# stm32devboard_f401ccu6.net
KiCad netlist of a schematic drawn in EasyEDA Pro
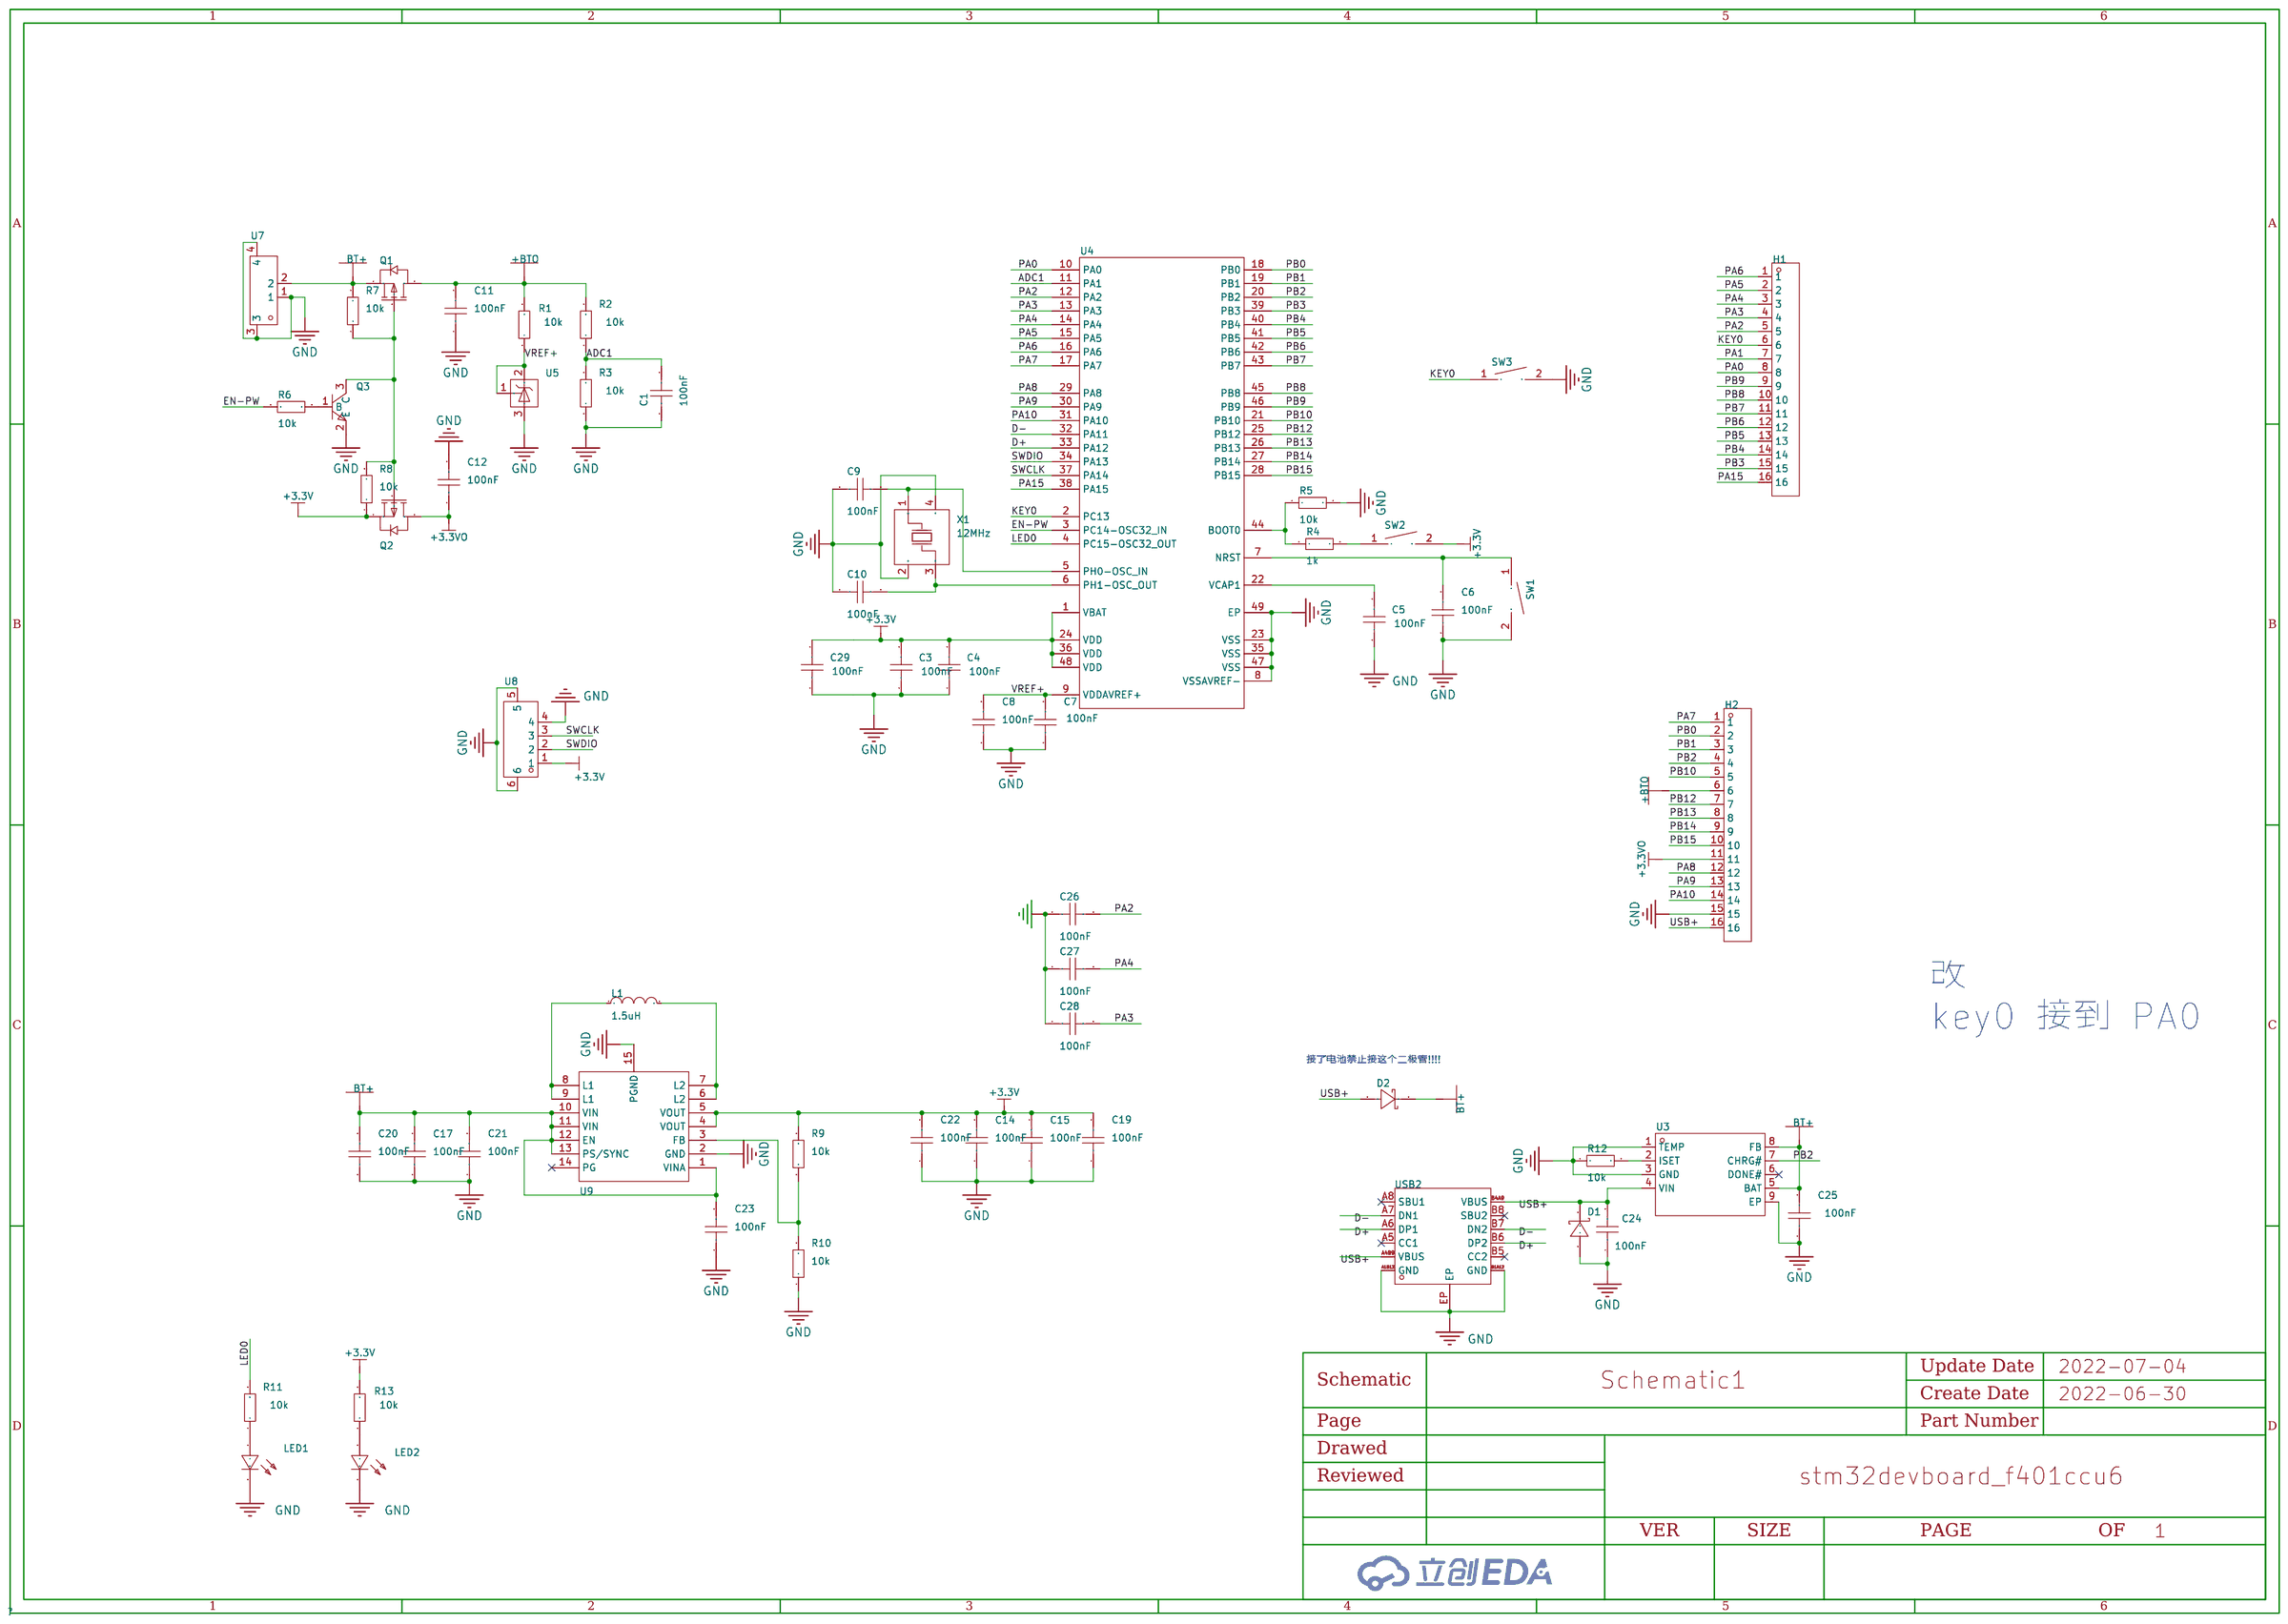
[diagram p0: schematic sheet]

(export (version "E")
  (design (tool "Eeschema 10.0.6"))
  (components
    (comp (ref "C1")
      (value "100nF")
      (footprint "easyedapro:C0402")
      (description "容值:100nF;精度:±10%;额定电压:25V;温度系数:X7R;")
      (fields (field (name "Manufacturer Part") "FN15X104K250PNG") (field (name "Manufacturer") "PSA(信昌电陶)"))
      (libsource (lib "easyedapro") (part "FN15X104K250PNG"))
    )
    (comp (ref "C3")
      (value "100nF")
      (footprint "easyedapro:C0603")
      (description "容值:100nF;精度:±10%;额定电压:50V;温度系数:X7R;")
      (fields
        (field (name "Manufacturer Part") "CC0603KRX7R9BB104")
        (field (name "Manufacturer") "YAGEO(国巨)")
      )
      (libsource (lib "easyedapro") (part "CC0603KRX7R9BB104"))
    )
    (comp (ref "C4")
      (value "100nF")
      (footprint "easyedapro:C0603")
      (description "容值:100nF;精度:±10%;额定电压:50V;温度系数:X7R;")
      (fields
        (field (name "Manufacturer Part") "CC0603KRX7R9BB104")
        (field (name "Manufacturer") "YAGEO(国巨)")
      )
      (libsource (lib "easyedapro") (part "CC0603KRX7R9BB104"))
    )
    (comp (ref "C5")
      (value "100nF")
      (footprint "easyedapro:C0603")
      (description "容值:100nF;精度:±10%;额定电压:50V;温度系数:X7R;")
      (fields
        (field (name "Manufacturer Part") "CC0603KRX7R9BB104")
        (field (name "Manufacturer") "YAGEO(国巨)")
      )
      (libsource (lib "easyedapro") (part "CC0603KRX7R9BB104"))
    )
    (comp (ref "C6")
      (value "100nF")
      (footprint "easyedapro:C0603")
      (description "容值:100nF;精度:±10%;额定电压:50V;温度系数:X7R;")
      (fields
        (field (name "Manufacturer Part") "CC0603KRX7R9BB104")
        (field (name "Manufacturer") "YAGEO(国巨)")
      )
      (libsource (lib "easyedapro") (part "CC0603KRX7R9BB104"))
    )
    (comp (ref "C7")
      (value "100nF")
      (footprint "easyedapro:C0603")
      (description "容值:100nF;精度:±10%;额定电压:50V;温度系数:X7R;")
      (fields
        (field (name "Manufacturer Part") "CC0603KRX7R9BB104")
        (field (name "Manufacturer") "YAGEO(国巨)")
      )
      (libsource (lib "easyedapro") (part "CC0603KRX7R9BB104"))
    )
    (comp (ref "C8")
      (value "100nF")
      (footprint "easyedapro:C0603")
      (description "容值:100nF;精度:±10%;额定电压:50V;温度系数:X7R;")
      (fields
        (field (name "Manufacturer Part") "CC0603KRX7R9BB104")
        (field (name "Manufacturer") "YAGEO(国巨)")
      )
      (libsource (lib "easyedapro") (part "CC0603KRX7R9BB104"))
    )
    (comp (ref "C9")
      (value "100nF")
      (footprint "easyedapro:C0603")
      (description "容值:100nF;精度:±10%;额定电压:50V;温度系数:X7R;")
      (fields
        (field (name "Manufacturer Part") "CC0603KRX7R9BB104")
        (field (name "Manufacturer") "YAGEO(国巨)")
      )
      (libsource (lib "easyedapro") (part "CC0603KRX7R9BB104"))
    )
    (comp (ref "C10")
      (value "100nF")
      (footprint "easyedapro:C0603")
      (description "容值:100nF;精度:±10%;额定电压:50V;温度系数:X7R;")
      (fields
        (field (name "Manufacturer Part") "CC0603KRX7R9BB104")
        (field (name "Manufacturer") "YAGEO(国巨)")
      )
      (libsource (lib "easyedapro") (part "CC0603KRX7R9BB104"))
    )
    (comp (ref "C11")
      (value "100nF")
      (footprint "easyedapro:C0603")
      (description "容值:100nF;精度:±10%;额定电压:50V;温度系数:X7R;")
      (fields
        (field (name "Manufacturer Part") "CC0603KRX7R9BB104")
        (field (name "Manufacturer") "YAGEO(国巨)")
      )
      (libsource (lib "easyedapro") (part "CC0603KRX7R9BB104"))
    )
    (comp (ref "C12")
      (value "100nF")
      (footprint "easyedapro:C0603")
      (description "容值:100nF;精度:±10%;额定电压:50V;温度系数:X7R;")
      (fields
        (field (name "Manufacturer Part") "CC0603KRX7R9BB104")
        (field (name "Manufacturer") "YAGEO(国巨)")
      )
      (libsource (lib "easyedapro") (part "CC0603KRX7R9BB104"))
    )
    (comp (ref "C14")
      (value "100nF")
      (footprint "easyedapro:C0603")
      (description "容值:100nF;精度:±10%;额定电压:50V;温度系数:X7R;")
      (fields
        (field (name "Manufacturer Part") "CC0603KRX7R9BB104")
        (field (name "Manufacturer") "YAGEO(国巨)")
      )
      (libsource (lib "easyedapro") (part "CC0603KRX7R9BB104"))
    )
    (comp (ref "C15")
      (value "100nF")
      (footprint "easyedapro:C0603")
      (description "容值:100nF;精度:±10%;额定电压:50V;温度系数:X7R;")
      (fields
        (field (name "Manufacturer Part") "CC0603KRX7R9BB104")
        (field (name "Manufacturer") "YAGEO(国巨)")
      )
      (libsource (lib "easyedapro") (part "CC0603KRX7R9BB104"))
    )
    (comp (ref "C17")
      (value "100nF")
      (footprint "easyedapro:C0603")
      (description "容值:100nF;精度:±10%;额定电压:50V;温度系数:X7R;")
      (fields
        (field (name "Manufacturer Part") "CC0603KRX7R9BB104")
        (field (name "Manufacturer") "YAGEO(国巨)")
      )
      (libsource (lib "easyedapro") (part "CC0603KRX7R9BB104"))
    )
    (comp (ref "C19")
      (value "100nF")
      (footprint "easyedapro:C0603")
      (description "容值:100nF;精度:±10%;额定电压:50V;温度系数:X7R;")
      (fields
        (field (name "Manufacturer Part") "CC0603KRX7R9BB104")
        (field (name "Manufacturer") "YAGEO(国巨)")
      )
      (libsource (lib "easyedapro") (part "CC0603KRX7R9BB104"))
    )
    (comp (ref "C20")
      (value "100nF")
      (footprint "easyedapro:C0603")
      (description "容值:100nF;精度:±10%;额定电压:50V;温度系数:X7R;")
      (fields
        (field (name "Manufacturer Part") "CC0603KRX7R9BB104")
        (field (name "Manufacturer") "YAGEO(国巨)")
      )
      (libsource (lib "easyedapro") (part "CC0603KRX7R9BB104"))
    )
    (comp (ref "C21")
      (value "100nF")
      (footprint "easyedapro:C0402")
      (description "容值:100nF;精度:±10%;额定电压:25V;温度系数:X7R;")
      (fields (field (name "Manufacturer Part") "FN15X104K250PNG") (field (name "Manufacturer") "PSA(信昌电陶)"))
      (libsource (lib "easyedapro") (part "FN15X104K250PNG"))
    )
    (comp (ref "C22")
      (value "100nF")
      (footprint "easyedapro:C0402")
      (description "容值:100nF;精度:±10%;额定电压:25V;温度系数:X7R;")
      (fields (field (name "Manufacturer Part") "FN15X104K250PNG") (field (name "Manufacturer") "PSA(信昌电陶)"))
      (libsource (lib "easyedapro") (part "FN15X104K250PNG"))
    )
    (comp (ref "C23")
      (value "100nF")
      (footprint "easyedapro:C0603")
      (description "容值:100nF;精度:±10%;额定电压:50V;温度系数:X7R;")
      (fields
        (field (name "Manufacturer Part") "CC0603KRX7R9BB104")
        (field (name "Manufacturer") "YAGEO(国巨)")
      )
      (libsource (lib "easyedapro") (part "CC0603KRX7R9BB104"))
    )
    (comp (ref "C24")
      (value "100nF")
      (footprint "easyedapro:C0603")
      (description "容值:100nF;精度:±10%;额定电压:50V;温度系数:X7R;")
      (fields
        (field (name "Manufacturer Part") "CC0603KRX7R9BB104")
        (field (name "Manufacturer") "YAGEO(国巨)")
      )
      (libsource (lib "easyedapro") (part "CC0603KRX7R9BB104"))
    )
    (comp (ref "C25")
      (value "100nF")
      (footprint "easyedapro:C0603")
      (description "容值:100nF;精度:±10%;额定电压:50V;温度系数:X7R;")
      (fields
        (field (name "Manufacturer Part") "CC0603KRX7R9BB104")
        (field (name "Manufacturer") "YAGEO(国巨)")
      )
      (libsource (lib "easyedapro") (part "CC0603KRX7R9BB104"))
    )
    (comp (ref "C26")
      (value "100nF")
      (footprint "easyedapro:C0402")
      (description "容值:100nF;精度:±10%;额定电压:25V;温度系数:X7R;")
      (fields (field (name "Manufacturer Part") "FN15X104K250PNG") (field (name "Manufacturer") "PSA(信昌电陶)"))
      (libsource (lib "easyedapro") (part "FN15X104K250PNG"))
    )
    (comp (ref "C27")
      (value "100nF")
      (footprint "easyedapro:C0402")
      (description "容值:100nF;精度:±10%;额定电压:25V;温度系数:X7R;")
      (fields (field (name "Manufacturer Part") "FN15X104K250PNG") (field (name "Manufacturer") "PSA(信昌电陶)"))
      (libsource (lib "easyedapro") (part "FN15X104K250PNG"))
    )
    (comp (ref "C28")
      (value "100nF")
      (footprint "easyedapro:C0402")
      (description "容值:100nF;精度:±10%;额定电压:25V;温度系数:X7R;")
      (fields (field (name "Manufacturer Part") "FN15X104K250PNG") (field (name "Manufacturer") "PSA(信昌电陶)"))
      (libsource (lib "easyedapro") (part "FN15X104K250PNG"))
    )
    (comp (ref "C29")
      (value "100nF")
      (footprint "easyedapro:C0402")
      (description "容值:100nF;精度:±10%;额定电压:25V;温度系数:X7R;")
      (fields (field (name "Manufacturer Part") "FN15X104K250PNG") (field (name "Manufacturer") "PSA(信昌电陶)"))
      (libsource (lib "easyedapro") (part "FN15X104K250PNG"))
    )
    (comp (ref "D1")
      (value "~")
      (footprint "easyedapro:SOD-123FL_L2.6-W1.6-LS3.4-R-FD")
      (description "极性:单向;反向截止电压(Vrwm):5V;击穿电压(最小值):6.4V;峰值脉冲电流(Ipp)@10/1000s:21.7A;最大钳位电压:9.4V;")
      (fields (field (name "Manufacturer Part") "SMFJ5.0A") (field (name "Manufacturer") "BORN伯恩半导体"))
      (libsource (lib "easyedapro") (part "SMFJ5.0A_C151893"))
    )
    (comp (ref "D2")
      (value "~")
      (footprint "easyedapro:SOD-323_L1.6-W1.3-LS2.7-RD")
      (description "二极管配置:独立式;直流反向耐压(Vr):40V;平均整流电流(Io):350mA;正向压降(Vf):600mV@200mA;反向电流(Ir):5A@30V;")
      (fields (field (name "Manufacturer Part") "1N5819WS S4") (field (name "Manufacturer") "JSMSEMI(杰盛微)"))
      (libsource (lib "easyedapro") (part "1N5819WS S4"))
    )
    (comp (ref "H1")
      (value "~")
      (footprint "easyedapro:HDR-TH_16P-P2.54-V-M")
      (description "2.54mm 圆孔排针,单排,180度,塑高3.0mm,塑宽2.54mm,D4.3mm,L=12.20mm,PPS料,镀金,16P")
      (fields
        (field (name "Manufacturer Part") "X5511WV-16-C396D43-1220")
        (field (name "Manufacturer") "XKB Connectivity(中国星坤)")
      )
      (libsource (lib "easyedapro") (part "X5511WV-16-C396D43-1220"))
    )
    (comp (ref "H2")
      (value "~")
      (footprint "easyedapro:HDR-TH_16P-P2.54-V-M")
      (description "2.54mm 圆孔排针,单排,180度,塑高3.0mm,塑宽2.54mm,D4.3mm,L=12.20mm,PPS料,镀金,16P")
      (fields
        (field (name "Manufacturer Part") "X5511WV-16-C396D43-1220")
        (field (name "Manufacturer") "XKB Connectivity(中国星坤)")
      )
      (libsource (lib "easyedapro") (part "X5511WV-16-C396D43-1220"))
    )
    (comp (ref "L1")
      (value "1.5uH")
      (footprint "easyedapro:IND-SMD_L4.0-W4.0_FNR40XXS")
      (description "电感值:1.5uH;精度:±20%;额定电流:3.34A;直流电阻(DCR):26m;")
      (fields (field (name "Manufacturer Part") "FNR4030S1R5MT") (field (name "Manufacturer") "cjiang(长江微电)"))
      (libsource (lib "easyedapro") (part "FNR4030S1R5MT"))
    )
    (comp (ref "LED1")
      (value "~")
      (footprint "easyedapro:LED0603-R-RD")
      (description "照明颜色:翠绿;色温 - CCT（K）:-;主波长/色坐标:520~535nm;")
      (fields
        (field (name "Manufacturer Part") "19-217/GHC-YR1S2/3T")
        (field (name "Manufacturer") "EVERLIGHT(台湾亿光)")
      )
      (libsource (lib "easyedapro") (part "19-217/GHC-YR1S2/3T"))
    )
    (comp (ref "LED2")
      (value "~")
      (footprint "easyedapro:LED0603-R-RD")
      (description "照明颜色:翠绿;色温 - CCT（K）:-;主波长/色坐标:520~535nm;")
      (fields
        (field (name "Manufacturer Part") "19-217/GHC-YR1S2/3T")
        (field (name "Manufacturer") "EVERLIGHT(台湾亿光)")
      )
      (libsource (lib "easyedapro") (part "19-217/GHC-YR1S2/3T"))
    )
    (comp (ref "Q1")
      (value "~")
      (footprint "easyedapro:SOT-23-3_L2.9-W1.3-P1.90-LS2.4-TR")
      (fields (field (name "Manufacturer Part") "AP2301B") (field (name "Manufacturer") "ALLPOWER(铨力)"))
      (libsource (lib "easyedapro") (part "AP2301B"))
    )
    (comp (ref "Q2")
      (value "~")
      (footprint "easyedapro:SOT-23-3_L2.9-W1.3-P1.90-LS2.4-TR")
      (fields (field (name "Manufacturer Part") "AP2301B") (field (name "Manufacturer") "ALLPOWER(铨力)"))
      (libsource (lib "easyedapro") (part "AP2301B"))
    )
    (comp (ref "Q3")
      (value "~")
      (footprint "easyedapro:SOT-23-3_L2.9-W1.3-P1.90-LS2.4-BR")
      (fields (field (name "Manufacturer Part") "S8050 J3Y") (field (name "Manufacturer") "FOSAN(富信)"))
      (libsource (lib "easyedapro") (part "S8050_C2926165"))
    )
    (comp (ref "R1")
      (value "10k")
      (footprint "easyedapro:R0603")
      (description "电阻类型:薄膜电阻;阻值:10k;精度:±0.1%;功率:100mW;温度系数:±25ppm/;最大工作电压:75V;工作温度范围:-55~+155;")
      (fields
        (field (name "Manufacturer Part") "TR0603B10K0P0525Z")
        (field (name "Manufacturer") "EVER OHMS(天二科技)")
      )
      (libsource (lib "easyedapro") (part "R_0603_EU"))
    )
    (comp (ref "R2")
      (value "10k")
      (footprint "easyedapro:R0603")
      (description "电阻类型:薄膜电阻;阻值:10k;精度:±0.1%;功率:100mW;温度系数:±25ppm/;最大工作电压:75V;工作温度范围:-55~+155;")
      (fields
        (field (name "Manufacturer Part") "TR0603B10K0P0525Z")
        (field (name "Manufacturer") "EVER OHMS(天二科技)")
      )
      (libsource (lib "easyedapro") (part "R_0603_EU"))
    )
    (comp (ref "R3")
      (value "10k")
      (footprint "easyedapro:R0603")
      (description "电阻类型:薄膜电阻;阻值:10k;精度:±0.1%;功率:100mW;温度系数:±25ppm/;最大工作电压:75V;工作温度范围:-55~+155;")
      (fields
        (field (name "Manufacturer Part") "TR0603B10K0P0525Z")
        (field (name "Manufacturer") "EVER OHMS(天二科技)")
      )
      (libsource (lib "easyedapro") (part "R_0603_EU"))
    )
    (comp (ref "R4")
      (value "1k")
      (footprint "easyedapro:R0603")
      (description "电阻类型:薄膜电阻;阻值:10k;精度:±0.1%;功率:100mW;温度系数:±25ppm/;最大工作电压:75V;工作温度范围:-55~+155;")
      (fields
        (field (name "Manufacturer Part") "TR0603B10K0P0525Z")
        (field (name "Manufacturer") "EVER OHMS(天二科技)")
      )
      (libsource (lib "easyedapro") (part "R_0603_EU"))
    )
    (comp (ref "R5")
      (value "10k")
      (footprint "easyedapro:R0603")
      (description "电阻类型:薄膜电阻;阻值:10k;精度:±0.1%;功率:100mW;温度系数:±25ppm/;最大工作电压:75V;工作温度范围:-55~+155;")
      (fields
        (field (name "Manufacturer Part") "TR0603B10K0P0525Z")
        (field (name "Manufacturer") "EVER OHMS(天二科技)")
      )
      (libsource (lib "easyedapro") (part "R_0603_EU"))
    )
    (comp (ref "R6")
      (value "10k")
      (footprint "easyedapro:R0603")
      (description "电阻类型:薄膜电阻;阻值:10k;精度:±0.1%;功率:100mW;温度系数:±25ppm/;最大工作电压:75V;工作温度范围:-55~+155;")
      (fields
        (field (name "Manufacturer Part") "TR0603B10K0P0525Z")
        (field (name "Manufacturer") "EVER OHMS(天二科技)")
      )
      (libsource (lib "easyedapro") (part "R_0603_EU"))
    )
    (comp (ref "R7")
      (value "10k")
      (footprint "easyedapro:R0603")
      (description "电阻类型:薄膜电阻;阻值:10k;精度:±0.1%;功率:100mW;温度系数:±25ppm/;最大工作电压:75V;工作温度范围:-55~+155;")
      (fields
        (field (name "Manufacturer Part") "TR0603B10K0P0525Z")
        (field (name "Manufacturer") "EVER OHMS(天二科技)")
      )
      (libsource (lib "easyedapro") (part "R_0603_EU"))
    )
    (comp (ref "R8")
      (value "10k")
      (footprint "easyedapro:R0603")
      (description "电阻类型:薄膜电阻;阻值:10k;精度:±0.1%;功率:100mW;温度系数:±25ppm/;最大工作电压:75V;工作温度范围:-55~+155;")
      (fields
        (field (name "Manufacturer Part") "TR0603B10K0P0525Z")
        (field (name "Manufacturer") "EVER OHMS(天二科技)")
      )
      (libsource (lib "easyedapro") (part "R_0603_EU"))
    )
    (comp (ref "R9")
      (value "10k")
      (footprint "easyedapro:R0603")
      (description "电阻类型:薄膜电阻;阻值:10k;精度:±0.1%;功率:100mW;温度系数:±25ppm/;最大工作电压:75V;工作温度范围:-55~+155;")
      (fields
        (field (name "Manufacturer Part") "TR0603B10K0P0525Z")
        (field (name "Manufacturer") "EVER OHMS(天二科技)")
      )
      (libsource (lib "easyedapro") (part "R_0603_EU"))
    )
    (comp (ref "R10")
      (value "10k")
      (footprint "easyedapro:R0603")
      (description "电阻类型:薄膜电阻;阻值:10k;精度:±0.1%;功率:100mW;温度系数:±25ppm/;最大工作电压:75V;工作温度范围:-55~+155;")
      (fields
        (field (name "Manufacturer Part") "TR0603B10K0P0525Z")
        (field (name "Manufacturer") "EVER OHMS(天二科技)")
      )
      (libsource (lib "easyedapro") (part "R_0603_EU"))
    )
    (comp (ref "R11")
      (value "10k")
      (footprint "easyedapro:R0603")
      (description "电阻类型:薄膜电阻;阻值:10k;精度:±0.1%;功率:100mW;温度系数:±25ppm/;最大工作电压:75V;工作温度范围:-55~+155;")
      (fields
        (field (name "Manufacturer Part") "TR0603B10K0P0525Z")
        (field (name "Manufacturer") "EVER OHMS(天二科技)")
      )
      (libsource (lib "easyedapro") (part "R_0603_EU"))
    )
    (comp (ref "R12")
      (value "10k")
      (footprint "easyedapro:R0603")
      (description "电阻类型:薄膜电阻;阻值:10k;精度:±0.1%;功率:100mW;温度系数:±25ppm/;最大工作电压:75V;工作温度范围:-55~+155;")
      (fields
        (field (name "Manufacturer Part") "TR0603B10K0P0525Z")
        (field (name "Manufacturer") "EVER OHMS(天二科技)")
      )
      (libsource (lib "easyedapro") (part "R_0603_EU"))
    )
    (comp (ref "R13")
      (value "10k")
      (footprint "easyedapro:R0603")
      (description "电阻类型:薄膜电阻;阻值:10k;精度:±0.1%;功率:100mW;温度系数:±25ppm/;最大工作电压:75V;工作温度范围:-55~+155;")
      (fields
        (field (name "Manufacturer Part") "TR0603B10K0P0525Z")
        (field (name "Manufacturer") "EVER OHMS(天二科技)")
      )
      (libsource (lib "easyedapro") (part "R_0603_EU"))
    )
    (comp (ref "SW1")
      (value "~")
      (footprint "easyedapro:SW-SMD_L4.0-W2.9-LS5.0")
      (fields
        (field (name "Manufacturer Part") "TSA343G00-250J2")
        (field (name "Manufacturer") "BRIGHT(博瑞泰)")
      )
      (libsource (lib "easyedapro") (part "TSA343G00-250J2"))
    )
    (comp (ref "SW2")
      (value "~")
      (footprint "easyedapro:SW-SMD_L4.0-W2.9-LS5.0")
      (fields
        (field (name "Manufacturer Part") "TSA343G00-250J2")
        (field (name "Manufacturer") "BRIGHT(博瑞泰)")
      )
      (libsource (lib "easyedapro") (part "TSA343G00-250J2"))
    )
    (comp (ref "SW3")
      (value "~")
      (footprint "easyedapro:SW-SMD_L4.0-W2.9-LS5.0")
      (fields
        (field (name "Manufacturer Part") "TSA343G00-250J2")
        (field (name "Manufacturer") "BRIGHT(博瑞泰)")
      )
      (libsource (lib "easyedapro") (part "TSA343G00-250J2"))
    )
    (comp (ref "U3")
      (value "~")
      (footprint "easyedapro:SOP-8_L4.9-W3.9-P1.27-LS6.0-BL-EP")
      (description "充电电池的类型:-;电池单元组数:-;最大充电电流:-;充满的电池组电压:-;最大供应电压:-;")
      (fields (field (name "Manufacturer Part") "CN3058E") (field (name "Manufacturer") "CONSONANCE(上海如韵)"))
      (libsource (lib "easyedapro") (part "CN3058E"))
    )
    (comp (ref "U4")
      (value "~")
      (footprint "easyedapro:UFQFPN-48_L7.0-W7.0-P0.50-BL-EP")
      (description "主频（MAX):84MHz;工作电压:1.7V ~ 3.6V;")
      (fields (field (name "Manufacturer Part") "STM32F401CEU6") (field (name "Manufacturer") "ST(意法半导体)"))
      (libsource (lib "easyedapro") (part "STM32F401CEU6"))
    )
    (comp (ref "U5")
      (value "~")
      (footprint "easyedapro:SOT-23-3_L2.9-W1.3-P1.90-LS2.4-BR")
      (fields (field (name "Manufacturer Part") "TL431") (field (name "Manufacturer") "MSKSEMI(美森科)"))
      (libsource (lib "easyedapro") (part "TL431_C2914425"))
    )
    (comp (ref "U7")
      (value "~")
      (footprint "easyedapro:CONN-SMD_2P-P1.25_GH1.25-2P")
      (fields
        (field (name "Manufacturer Part") "GH1.25-2PLTPZ")
        (field (name "Manufacturer") "BOOMELE(博穆精密)")
      )
      (libsource (lib "easyedapro") (part "GH1.25-2PLTPZ"))
    )
    (comp (ref "U8")
      (value "~")
      (footprint "easyedapro:CONN-TH_4P-P1.25_XUNPU_WAFER-GH1.25-4PLB")
      (fields
        (field (name "Manufacturer Part") "WAFER-GH1.25-4PLB")
        (field (name "Manufacturer") "XUNPU(讯普)")
      )
      (libsource (lib "easyedapro") (part "WAFER-GH1.25-4PLB"))
    )
    (comp (ref "U9")
      (value "~")
      (footprint "easyedapro:VSON-14_L4.0-W3.0-P0.50-BL-EP_TI_DSJ")
      (description "功能类型:升降压型;同步整流:是;输出通道数:1;拓扑结构:降压-升压式;输入电压:1.8V~5.5V;输出电压:1.2V~5.5V;输出电流(最大值):3.5A;开关频率:2.4MHz;")
      (fields (field (name "Manufacturer Part") "TPS63020DSJR") (field (name "Manufacturer") "TI(德州仪器)"))
      (libsource (lib "easyedapro") (part "TPS63020DSJR"))
    )
    (comp (ref "USB2")
      (value "~")
      (footprint "easyedapro:USB-C-SMD_TYPE-C-16P-1")
      (description "连接器类型:Type-C;公母:母座;触点数量:16;端口数量:1;安装方式:卧贴;额定电流 - 电源:3A;工作温度范围:-40~+85;")
      (fields (field (name "Manufacturer Part") "TYPEC-304-ACP16") (field (name "Manufacturer") "XUNPU(讯普)"))
      (libsource (lib "easyedapro") (part "TYPEC-304-ACP16"))
    )
    (comp (ref "X1")
      (value "12MHz")
      (footprint "easyedapro:OSC-SMD_4P-L3.2-W2.5-BL")
      (description "晶振类型:贴片无源晶振;频率:12MHz;频率公差:±10ppm;频率稳定度:±30ppm;负载电容:20pF;工作温度:-40~+85;")
      (fields (field (name "Manufacturer Part") "X322512MSB4SI") (field (name "Manufacturer") "YXC扬兴科技"))
      (libsource (lib "easyedapro") (part "X322512MSB4SI"))
    )
  )
  (nets
    (net (code "1") (name "+3.3V") (class "Default")
      (node (ref "C14") (pin "2") (pinfunction "2_2") (pintype "input"))
      (node (ref "C15") (pin "2") (pinfunction "2_2") (pintype "input"))
      (node (ref "C19") (pin "2") (pinfunction "2_2") (pintype "input"))
      (node (ref "C22") (pin "2") (pinfunction "2_2") (pintype "input"))
      (node (ref "C29") (pin "2") (pinfunction "2_2") (pintype "input"))
      (node (ref "C3") (pin "2") (pinfunction "2_2") (pintype "input"))
      (node (ref "C4") (pin "2") (pinfunction "2_2") (pintype "input"))
      (node (ref "Q2") (pin "1") (pinfunction "S_1") (pintype "input"))
      (node (ref "R13") (pin "2") (pinfunction "2_2") (pintype "input"))
      (node (ref "R8") (pin "1") (pinfunction "1_1") (pintype "input"))
      (node (ref "R9") (pin "2") (pinfunction "2_2") (pintype "input"))
      (node (ref "SW2") (pin "2") (pinfunction "2_2") (pintype "input"))
      (node (ref "U4") (pin "1") (pinfunction "VBAT_1") (pintype "input"))
      (node (ref "U4") (pin "24") (pinfunction "VDD_24") (pintype "input"))
      (node (ref "U4") (pin "36") (pinfunction "VDD_36") (pintype "input"))
      (node (ref "U4") (pin "48") (pinfunction "VDD_48") (pintype "input"))
      (node (ref "U8") (pin "1") (pinfunction "1_1") (pintype "input"))
      (node (ref "U9") (pin "4") (pinfunction "VOUT_4") (pintype "input"))
      (node (ref "U9") (pin "5") (pinfunction "VOUT_5") (pintype "input"))
    )
    (net (code "2") (name "+3.3VO") (class "Default")
      (node (ref "C12") (pin "1") (pinfunction "1_1") (pintype "input"))
      (node (ref "H2") (pin "11") (pinfunction "11_11") (pintype "input"))
      (node (ref "Q2") (pin "3") (pinfunction "D_3") (pintype "input"))
    )
    (net (code "3") (name "+BTO") (class "Default")
      (node (ref "C11") (pin "2") (pinfunction "2_2") (pintype "input"))
      (node (ref "H2") (pin "6") (pinfunction "6_6") (pintype "input"))
      (node (ref "Q1") (pin "3") (pinfunction "D_3") (pintype "input"))
      (node (ref "R1") (pin "2") (pinfunction "2_2") (pintype "input"))
      (node (ref "R2") (pin "2") (pinfunction "2_2") (pintype "input"))
    )
    (net (code "4") (name "/ADC1") (class "Default")
      (node (ref "C1") (pin "2") (pinfunction "2_2") (pintype "input"))
      (node (ref "R2") (pin "1") (pinfunction "1_1") (pintype "input"))
      (node (ref "R3") (pin "2") (pinfunction "2_2") (pintype "input"))
      (node (ref "U4") (pin "11") (pinfunction "PA1_11") (pintype "bidirectional"))
    )
    (net (code "5") (name "/D+") (class "Default")
      (node (ref "U4") (pin "33") (pinfunction "PA12_33") (pintype "bidirectional"))
      (node (ref "USB2") (pin "A6") (pinfunction "DP1_A6") (pintype "input"))
      (node (ref "USB2") (pin "B6") (pinfunction "DP2_B6") (pintype "input"))
    )
    (net (code "6") (name "/D-") (class "Default")
      (node (ref "U4") (pin "32") (pinfunction "PA11_32") (pintype "bidirectional"))
      (node (ref "USB2") (pin "A7") (pinfunction "DN1_A7") (pintype "input"))
      (node (ref "USB2") (pin "B7") (pinfunction "DN2_B7") (pintype "input"))
    )
    (net (code "7") (name "/EN-PW") (class "Default")
      (node (ref "R6") (pin "1") (pinfunction "1_1") (pintype "input"))
      (node (ref "U4") (pin "3") (pinfunction "PC14-OSC32_IN_3") (pintype "bidirectional"))
    )
    (net (code "8") (name "/KEY0") (class "Default")
      (node (ref "H1") (pin "6") (pinfunction "6_6") (pintype "input"))
      (node (ref "SW3") (pin "1") (pinfunction "1_1") (pintype "input"))
      (node (ref "U4") (pin "2") (pinfunction "PC13_2") (pintype "bidirectional"))
    )
    (net (code "9") (name "/LED0") (class "Default")
      (node (ref "R11") (pin "2") (pinfunction "2_2") (pintype "input"))
      (node (ref "U4") (pin "4") (pinfunction "PC15-OSC32_OUT_4") (pintype "bidirectional"))
    )
    (net (code "10") (name "/PA0") (class "Default")
      (node (ref "H1") (pin "8") (pinfunction "8_8") (pintype "input"))
      (node (ref "U4") (pin "10") (pinfunction "PA0_10") (pintype "bidirectional"))
    )
    (net (code "11") (name "/PA1") (class "Default")
      (node (ref "H1") (pin "7") (pinfunction "7_7") (pintype "input"))
    )
    (net (code "12") (name "/PA2") (class "Default")
      (node (ref "C26") (pin "2") (pinfunction "2_2") (pintype "input"))
      (node (ref "H1") (pin "5") (pinfunction "5_5") (pintype "input"))
      (node (ref "U4") (pin "12") (pinfunction "PA2_12") (pintype "bidirectional"))
    )
    (net (code "13") (name "/PA3") (class "Default")
      (node (ref "C28") (pin "2") (pinfunction "2_2") (pintype "input"))
      (node (ref "H1") (pin "4") (pinfunction "4_4") (pintype "input"))
      (node (ref "U4") (pin "13") (pinfunction "PA3_13") (pintype "bidirectional"))
    )
    (net (code "14") (name "/PA4") (class "Default")
      (node (ref "C27") (pin "2") (pinfunction "2_2") (pintype "input"))
      (node (ref "H1") (pin "3") (pinfunction "3_3") (pintype "input"))
      (node (ref "U4") (pin "14") (pinfunction "PA4_14") (pintype "bidirectional"))
    )
    (net (code "15") (name "/PA5") (class "Default")
      (node (ref "H1") (pin "2") (pinfunction "2_2") (pintype "input"))
      (node (ref "U4") (pin "15") (pinfunction "PA5_15") (pintype "bidirectional"))
    )
    (net (code "16") (name "/PA6") (class "Default")
      (node (ref "H1") (pin "1") (pinfunction "1_1") (pintype "input"))
      (node (ref "U4") (pin "16") (pinfunction "PA6_16") (pintype "bidirectional"))
    )
    (net (code "17") (name "/PA7") (class "Default")
      (node (ref "H2") (pin "1") (pinfunction "1_1") (pintype "input"))
      (node (ref "U4") (pin "17") (pinfunction "PA7_17") (pintype "bidirectional"))
    )
    (net (code "18") (name "/PA8") (class "Default")
      (node (ref "H2") (pin "12") (pinfunction "12_12") (pintype "input"))
      (node (ref "U4") (pin "29") (pinfunction "PA8_29") (pintype "bidirectional"))
    )
    (net (code "19") (name "/PA9") (class "Default")
      (node (ref "H2") (pin "13") (pinfunction "13_13") (pintype "input"))
      (node (ref "U4") (pin "30") (pinfunction "PA9_30") (pintype "bidirectional"))
    )
    (net (code "20") (name "/PA10") (class "Default")
      (node (ref "H2") (pin "14") (pinfunction "14_14") (pintype "input"))
      (node (ref "U4") (pin "31") (pinfunction "PA10_31") (pintype "bidirectional"))
    )
    (net (code "21") (name "/PA15") (class "Default")
      (node (ref "H1") (pin "16") (pinfunction "16_16") (pintype "input"))
      (node (ref "U4") (pin "38") (pinfunction "PA15_38") (pintype "bidirectional"))
    )
    (net (code "22") (name "/PB0") (class "Default")
      (node (ref "H2") (pin "2") (pinfunction "2_2") (pintype "input"))
      (node (ref "U4") (pin "18") (pinfunction "PB0_18") (pintype "bidirectional"))
    )
    (net (code "23") (name "/PB1") (class "Default")
      (node (ref "H2") (pin "3") (pinfunction "3_3") (pintype "input"))
      (node (ref "U4") (pin "19") (pinfunction "PB1_19") (pintype "bidirectional"))
    )
    (net (code "24") (name "/PB2") (class "Default")
      (node (ref "H2") (pin "4") (pinfunction "4_4") (pintype "input"))
      (node (ref "U3") (pin "7") (pinfunction "CHRG#_7") (pintype "input"))
      (node (ref "U4") (pin "20") (pinfunction "PB2_20") (pintype "bidirectional"))
    )
    (net (code "25") (name "/PB3") (class "Default")
      (node (ref "H1") (pin "15") (pinfunction "15_15") (pintype "input"))
      (node (ref "U4") (pin "39") (pinfunction "PB3_39") (pintype "bidirectional"))
    )
    (net (code "26") (name "/PB4") (class "Default")
      (node (ref "H1") (pin "14") (pinfunction "14_14") (pintype "input"))
      (node (ref "U4") (pin "40") (pinfunction "PB4_40") (pintype "bidirectional"))
    )
    (net (code "27") (name "/PB5") (class "Default")
      (node (ref "H1") (pin "13") (pinfunction "13_13") (pintype "input"))
      (node (ref "U4") (pin "41") (pinfunction "PB5_41") (pintype "bidirectional"))
    )
    (net (code "28") (name "/PB6") (class "Default")
      (node (ref "H1") (pin "12") (pinfunction "12_12") (pintype "input"))
      (node (ref "U4") (pin "42") (pinfunction "PB6_42") (pintype "bidirectional"))
    )
    (net (code "29") (name "/PB7") (class "Default")
      (node (ref "H1") (pin "11") (pinfunction "11_11") (pintype "input"))
      (node (ref "U4") (pin "43") (pinfunction "PB7_43") (pintype "bidirectional"))
    )
    (net (code "30") (name "/PB8") (class "Default")
      (node (ref "H1") (pin "10") (pinfunction "10_10") (pintype "input"))
      (node (ref "U4") (pin "45") (pinfunction "PB8_45") (pintype "bidirectional"))
    )
    (net (code "31") (name "/PB9") (class "Default")
      (node (ref "H1") (pin "9") (pinfunction "9_9") (pintype "input"))
      (node (ref "U4") (pin "46") (pinfunction "PB9_46") (pintype "bidirectional"))
    )
    (net (code "32") (name "/PB10") (class "Default")
      (node (ref "H2") (pin "5") (pinfunction "5_5") (pintype "input"))
      (node (ref "U4") (pin "21") (pinfunction "PB10_21") (pintype "bidirectional"))
    )
    (net (code "33") (name "/PB12") (class "Default")
      (node (ref "H2") (pin "7") (pinfunction "7_7") (pintype "input"))
      (node (ref "U4") (pin "25") (pinfunction "PB12_25") (pintype "bidirectional"))
    )
    (net (code "34") (name "/PB13") (class "Default")
      (node (ref "H2") (pin "8") (pinfunction "8_8") (pintype "input"))
      (node (ref "U4") (pin "26") (pinfunction "PB13_26") (pintype "bidirectional"))
    )
    (net (code "35") (name "/PB14") (class "Default")
      (node (ref "H2") (pin "9") (pinfunction "9_9") (pintype "input"))
      (node (ref "U4") (pin "27") (pinfunction "PB14_27") (pintype "bidirectional"))
    )
    (net (code "36") (name "/PB15") (class "Default")
      (node (ref "H2") (pin "10") (pinfunction "10_10") (pintype "input"))
      (node (ref "U4") (pin "28") (pinfunction "PB15_28") (pintype "bidirectional"))
    )
    (net (code "37") (name "/SWCLK") (class "Default")
      (node (ref "U4") (pin "37") (pinfunction "PA14_37") (pintype "bidirectional"))
      (node (ref "U8") (pin "3") (pinfunction "3_3") (pintype "input"))
    )
    (net (code "38") (name "/SWDIO") (class "Default")
      (node (ref "U4") (pin "34") (pinfunction "PA13_34") (pintype "bidirectional"))
      (node (ref "U8") (pin "2") (pinfunction "2_2") (pintype "input"))
    )
    (net (code "39") (name "/USB+") (class "Default")
      (node (ref "C24") (pin "2") (pinfunction "2_2") (pintype "input"))
      (node (ref "D1") (pin "1") (pinfunction "K_1") (pintype "input"))
      (node (ref "D2") (pin "2") (pinfunction "A_2") (pintype "input"))
      (node (ref "H2") (pin "16") (pinfunction "16_16") (pintype "input"))
      (node (ref "U3") (pin "4") (pinfunction "VIN_4") (pintype "input"))
      (node (ref "USB2") (pin "A4B9") (pinfunction "VBUS_A4B9") (pintype "input"))
      (node (ref "USB2") (pin "B4A9") (pinfunction "VBUS_B4A9") (pintype "input"))
    )
    (net (code "40") (name "/VREF+") (class "Default")
      (node (ref "C7") (pin "2") (pinfunction "2_2") (pintype "input"))
      (node (ref "C8") (pin "2") (pinfunction "2_2") (pintype "input"))
      (node (ref "R1") (pin "1") (pinfunction "1_1") (pintype "input"))
      (node (ref "U4") (pin "9") (pinfunction "VDDAVREF+_9") (pintype "input"))
      (node (ref "U5") (pin "1") (pinfunction "REF_1") (pintype "input"))
      (node (ref "U5") (pin "2") (pinfunction "C_2") (pintype "input"))
    )
    (net (code "41") (name "BT+") (class "Default")
      (node (ref "C17") (pin "2") (pinfunction "2_2") (pintype "input"))
      (node (ref "C20") (pin "2") (pinfunction "2_2") (pintype "input"))
      (node (ref "C21") (pin "2") (pinfunction "2_2") (pintype "input"))
      (node (ref "C23") (pin "2") (pinfunction "2_2") (pintype "input"))
      (node (ref "C25") (pin "2") (pinfunction "2_2") (pintype "input"))
      (node (ref "D2") (pin "1") (pinfunction "C_1") (pintype "input"))
      (node (ref "Q1") (pin "1") (pinfunction "S_1") (pintype "input"))
      (node (ref "R7") (pin "2") (pinfunction "2_2") (pintype "input"))
      (node (ref "U3") (pin "5") (pinfunction "BAT_5") (pintype "input"))
      (node (ref "U3") (pin "8") (pinfunction "FB_8") (pintype "input"))
      (node (ref "U7") (pin "2") (pinfunction "2_2") (pintype "input"))
      (node (ref "U9") (pin "1") (pinfunction "VINA_1") (pintype "input"))
      (node (ref "U9") (pin "10") (pinfunction "VIN_10") (pintype "input"))
      (node (ref "U9") (pin "11") (pinfunction "VIN_11") (pintype "input"))
      (node (ref "U9") (pin "12") (pinfunction "EN_12") (pintype "input"))
      (node (ref "U9") (pin "13") (pinfunction "PS/SYNC_13") (pintype "input"))
    )
    (net (code "42") (name "GND") (class "Default")
      (node (ref "C1") (pin "1") (pinfunction "1_1") (pintype "input"))
      (node (ref "C10") (pin "1") (pinfunction "1_1") (pintype "input"))
      (node (ref "C11") (pin "1") (pinfunction "1_1") (pintype "input"))
      (node (ref "C12") (pin "2") (pinfunction "2_2") (pintype "input"))
      (node (ref "C14") (pin "1") (pinfunction "1_1") (pintype "input"))
      (node (ref "C15") (pin "1") (pinfunction "1_1") (pintype "input"))
      (node (ref "C17") (pin "1") (pinfunction "1_1") (pintype "input"))
      (node (ref "C19") (pin "1") (pinfunction "1_1") (pintype "input"))
      (node (ref "C20") (pin "1") (pinfunction "1_1") (pintype "input"))
      (node (ref "C21") (pin "1") (pinfunction "1_1") (pintype "input"))
      (node (ref "C22") (pin "1") (pinfunction "1_1") (pintype "input"))
      (node (ref "C23") (pin "1") (pinfunction "1_1") (pintype "input"))
      (node (ref "C24") (pin "1") (pinfunction "1_1") (pintype "input"))
      (node (ref "C25") (pin "1") (pinfunction "1_1") (pintype "input"))
      (node (ref "C26") (pin "1") (pinfunction "1_1") (pintype "input"))
      (node (ref "C27") (pin "1") (pinfunction "1_1") (pintype "input"))
      (node (ref "C28") (pin "1") (pinfunction "1_1") (pintype "input"))
      (node (ref "C29") (pin "1") (pinfunction "1_1") (pintype "input"))
      (node (ref "C3") (pin "1") (pinfunction "1_1") (pintype "input"))
      (node (ref "C4") (pin "1") (pinfunction "1_1") (pintype "input"))
      (node (ref "C5") (pin "1") (pinfunction "1_1") (pintype "input"))
      (node (ref "C6") (pin "1") (pinfunction "1_1") (pintype "input"))
      (node (ref "C7") (pin "1") (pinfunction "1_1") (pintype "input"))
      (node (ref "C8") (pin "1") (pinfunction "1_1") (pintype "input"))
      (node (ref "C9") (pin "1") (pinfunction "1_1") (pintype "input"))
      (node (ref "D1") (pin "2") (pinfunction "A_2") (pintype "input"))
      (node (ref "H2") (pin "15") (pinfunction "15_15") (pintype "input"))
      (node (ref "LED1") (pin "2") (pinfunction "C_2") (pintype "input"))
      (node (ref "LED2") (pin "2") (pinfunction "C_2") (pintype "input"))
      (node (ref "Q3") (pin "2") (pinfunction "E_2") (pintype "input"))
      (node (ref "R10") (pin "1") (pinfunction "1_1") (pintype "input"))
      (node (ref "R12") (pin "1") (pinfunction "1_1") (pintype "input"))
      (node (ref "R3") (pin "1") (pinfunction "1_1") (pintype "input"))
      (node (ref "R5") (pin "2") (pinfunction "2_2") (pintype "input"))
      (node (ref "SW1") (pin "2") (pinfunction "2_2") (pintype "input"))
      (node (ref "SW3") (pin "2") (pinfunction "2_2") (pintype "input"))
      (node (ref "U3") (pin "1") (pinfunction "TEMP_1") (pintype "input"))
      (node (ref "U3") (pin "3") (pinfunction "GND_3") (pintype "input"))
      (node (ref "U3") (pin "9") (pinfunction "EP_9") (pintype "input"))
      (node (ref "U4") (pin "23") (pinfunction "VSS_23") (pintype "input"))
      (node (ref "U4") (pin "35") (pinfunction "VSS_35") (pintype "input"))
      (node (ref "U4") (pin "47") (pinfunction "VSS_47") (pintype "input"))
      (node (ref "U4") (pin "49") (pinfunction "EP_49") (pintype "input"))
      (node (ref "U4") (pin "8") (pinfunction "VSSAVREF-_8") (pintype "input"))
      (node (ref "U5") (pin "3") (pinfunction "A_3") (pintype "input"))
      (node (ref "U7") (pin "1") (pinfunction "1_1") (pintype "input"))
      (node (ref "U7") (pin "3") (pinfunction "3_3") (pintype "input"))
      (node (ref "U7") (pin "4") (pinfunction "4_4") (pintype "input"))
      (node (ref "U8") (pin "4") (pinfunction "4_4") (pintype "input"))
      (node (ref "U8") (pin "5") (pinfunction "5_5") (pintype "input"))
      (node (ref "U8") (pin "6") (pinfunction "6_6") (pintype "input"))
      (node (ref "U9") (pin "15") (pinfunction "PGND_15") (pintype "input"))
      (node (ref "U9") (pin "2") (pinfunction "GND_2") (pintype "input"))
      (node (ref "USB2") (pin "A1B12") (pinfunction "GND_A1B12") (pintype "input"))
      (node (ref "USB2") (pin "B1A12") (pinfunction "GND_B1A12") (pintype "input"))
      (node (ref "USB2") (pin "EP") (pinfunction "EP_EP") (pintype "input"))
      (node (ref "X1") (pin "2") (pinfunction "GND_2") (pintype "input"))
      (node (ref "X1") (pin "4") (pinfunction "GND_4") (pintype "input"))
    )
    (net (code "43") (name "Net-(L1-Pad1)") (class "Default")
      (node (ref "L1") (pin "1") (pinfunction "1_1") (pintype "input"))
      (node (ref "U9") (pin "8") (pinfunction "L1_8") (pintype "input"))
      (node (ref "U9") (pin "9") (pinfunction "L1_9") (pintype "input"))
    )
    (net (code "44") (name "Net-(L1-Pad2)") (class "Default")
      (node (ref "L1") (pin "2") (pinfunction "2_2") (pintype "input"))
      (node (ref "U9") (pin "6") (pinfunction "L2_6") (pintype "input"))
      (node (ref "U9") (pin "7") (pinfunction "L2_7") (pintype "input"))
    )
    (net (code "45") (name "Net-(LED1-A)") (class "Default")
      (node (ref "LED1") (pin "1") (pinfunction "A_1") (pintype "input"))
      (node (ref "R11") (pin "1") (pinfunction "1_1") (pintype "input"))
    )
    (net (code "46") (name "Net-(LED2-A)") (class "Default")
      (node (ref "LED2") (pin "1") (pinfunction "A_1") (pintype "input"))
      (node (ref "R13") (pin "1") (pinfunction "1_1") (pintype "input"))
    )
    (net (code "47") (name "Net-(Q1-G)") (class "Default")
      (node (ref "Q1") (pin "2") (pinfunction "G_2") (pintype "input"))
      (node (ref "Q2") (pin "2") (pinfunction "G_2") (pintype "input"))
      (node (ref "Q3") (pin "3") (pinfunction "C_3") (pintype "input"))
      (node (ref "R7") (pin "1") (pinfunction "1_1") (pintype "input"))
      (node (ref "R8") (pin "2") (pinfunction "2_2") (pintype "input"))
    )
    (net (code "48") (name "Net-(Q3-B)") (class "Default")
      (node (ref "Q3") (pin "1") (pinfunction "B_1") (pintype "input"))
      (node (ref "R6") (pin "2") (pinfunction "2_2") (pintype "input"))
    )
    (net (code "49") (name "Net-(R4-Pad2)") (class "Default")
      (node (ref "R4") (pin "2") (pinfunction "2_2") (pintype "input"))
      (node (ref "SW2") (pin "1") (pinfunction "1_1") (pintype "input"))
    )
    (net (code "50") (name "Net-(U3-ISET)") (class "Default")
      (node (ref "R12") (pin "2") (pinfunction "2_2") (pintype "input"))
      (node (ref "U3") (pin "2") (pinfunction "ISET_2") (pintype "input"))
    )
    (net (code "51") (name "Net-(U4-BOOT0)") (class "Default")
      (node (ref "R4") (pin "1") (pinfunction "1_1") (pintype "input"))
      (node (ref "R5") (pin "1") (pinfunction "1_1") (pintype "input"))
      (node (ref "U4") (pin "44") (pinfunction "BOOT0_44") (pintype "input"))
    )
    (net (code "52") (name "Net-(U4-NRST)") (class "Default")
      (node (ref "C6") (pin "2") (pinfunction "2_2") (pintype "input"))
      (node (ref "SW1") (pin "1") (pinfunction "1_1") (pintype "input"))
      (node (ref "U4") (pin "7") (pinfunction "NRST_7") (pintype "bidirectional"))
    )
    (net (code "53") (name "Net-(U4-PH0-OSC_IN)") (class "Default")
      (node (ref "C9") (pin "2") (pinfunction "2_2") (pintype "input"))
      (node (ref "U4") (pin "5") (pinfunction "PH0-OSC_IN_5") (pintype "bidirectional"))
      (node (ref "X1") (pin "1") (pinfunction "OSC1_1") (pintype "input"))
    )
    (net (code "54") (name "Net-(U4-PH1-OSC_OUT)") (class "Default")
      (node (ref "C10") (pin "2") (pinfunction "2_2") (pintype "input"))
      (node (ref "U4") (pin "6") (pinfunction "PH1-OSC_OUT_6") (pintype "bidirectional"))
      (node (ref "X1") (pin "3") (pinfunction "OSC2_3") (pintype "input"))
    )
    (net (code "55") (name "Net-(U4-VCAP1)") (class "Default")
      (node (ref "C5") (pin "2") (pinfunction "2_2") (pintype "input"))
      (node (ref "U4") (pin "22") (pinfunction "VCAP1_22") (pintype "input"))
    )
    (net (code "56") (name "Net-(U9-FB)") (class "Default")
      (node (ref "R10") (pin "2") (pinfunction "2_2") (pintype "input"))
      (node (ref "R9") (pin "1") (pinfunction "1_1") (pintype "input"))
      (node (ref "U9") (pin "3") (pinfunction "FB_3") (pintype "input"))
    )
    (net (code "57") (name "unconnected-(U3-DONE#-Pad6)") (class "Default")
      (node (ref "U3") (pin "6") (pinfunction "DONE#_6") (pintype "input+no_connect"))
    )
    (net (code "58") (name "unconnected-(U9-PG-Pad14)") (class "Default")
      (node (ref "U9") (pin "14") (pinfunction "PG_14") (pintype "input+no_connect"))
    )
    (net (code "59") (name "unconnected-(USB2-CC1-PadA5)") (class "Default")
      (node (ref "USB2") (pin "A5") (pinfunction "CC1_A5") (pintype "input+no_connect"))
    )
    (net (code "60") (name "unconnected-(USB2-CC2-PadB5)") (class "Default")
      (node (ref "USB2") (pin "B5") (pinfunction "CC2_B5") (pintype "input+no_connect"))
    )
    (net (code "61") (name "unconnected-(USB2-SBU1-PadA8)") (class "Default")
      (node (ref "USB2") (pin "A8") (pinfunction "SBU1_A8") (pintype "input+no_connect"))
    )
    (net (code "62") (name "unconnected-(USB2-SBU2-PadB8)") (class "Default")
      (node (ref "USB2") (pin "B8") (pinfunction "SBU2_B8") (pintype "input+no_connect"))
    )
  )
)
